# ProPrj_Flipper_-_TweenWave_2025-09-02.net
KiCad netlist of a schematic drawn in EasyEDA Pro
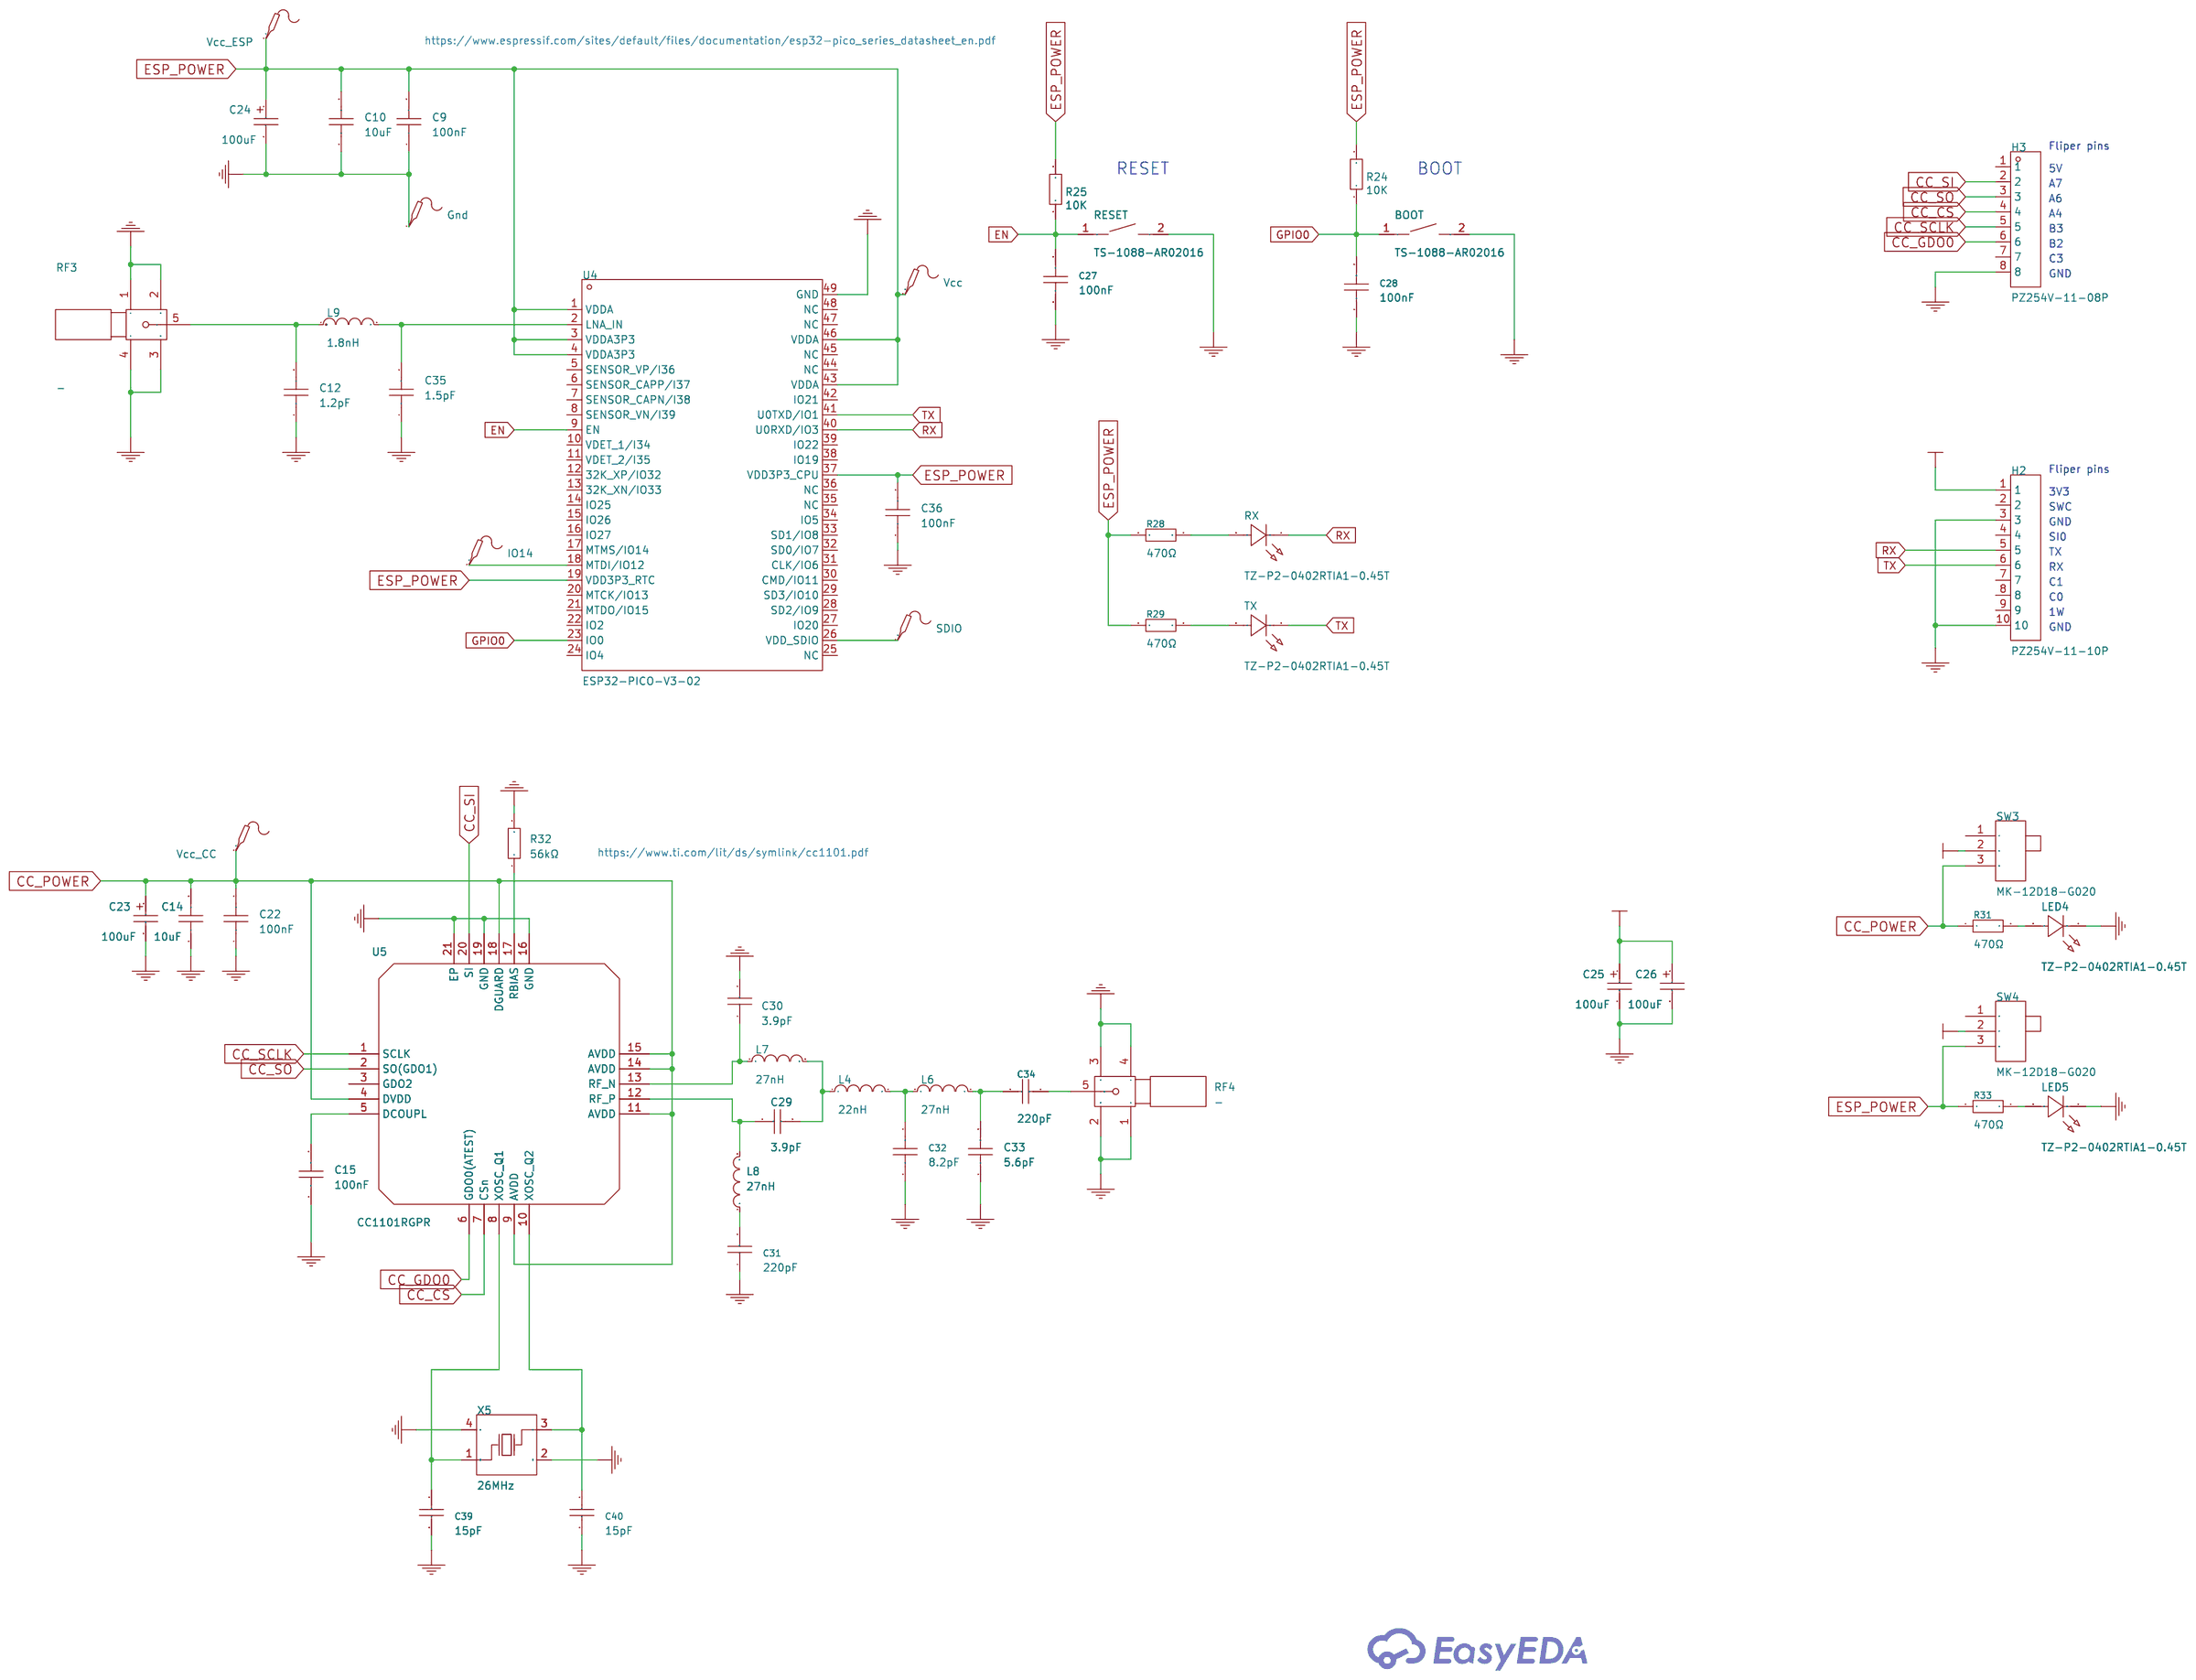
[diagram p0: schematic sheet]

(export (version "E")
  (design (tool "Eeschema 10.0.6"))
  (components
    (comp (ref "BOOT")
      (value "TS-1088-AR02016")
      (footprint "easyedapro:SW-SMD_L3.9-W3.0-P4.45")
      (fields (field (name "Manufacturer") "XUNPU(讯普)"))
      (libsource (lib "easyedapro") (part "TS-1088-AR02016"))
    )
    (comp (ref "C9")
      (value "100nF")
      (footprint "easyedapro:C0603")
      (description "Capacitance:100nF Tolerance:±10% Tolerance:±10% Voltage Rating:50V Temperature Coefficient:X7R")
      (fields
        (field (name "Manufacturer Part") "CC0603KRX7R9BB104")
        (field (name "Manufacturer") "YAGEO(国巨)")
      )
      (libsource (lib "easyedapro") (part "CC0603KRX7R9BB104"))
    )
    (comp (ref "C10")
      (value "10uF")
      (footprint "easyedapro:C0603")
      (fields
        (field (name "Manufacturer Part") "CL10A106MP8NNNC")
        (field (name "Manufacturer") "SAMSUNG(三星)")
      )
      (libsource (lib "easyedapro") (part "CL10A106MP8NNNC"))
    )
    (comp (ref "C12")
      (value "1.2pF")
      (footprint "easyedapro:C0201")
      (fields
        (field (name "Manufacturer Part") "GRM0335C1H1R2BA01D")
        (field (name "Manufacturer") "muRata(村田)")
      )
      (libsource (lib "easyedapro") (part "GRM0335C1H1R2BA01D"))
    )
    (comp (ref "C14")
      (value "10uF")
      (footprint "easyedapro:C0603")
      (fields
        (field (name "Manufacturer Part") "CL10A106MP8NNNC")
        (field (name "Manufacturer") "SAMSUNG(三星)")
      )
      (libsource (lib "easyedapro") (part "CL10A106MP8NNNC"))
    )
    (comp (ref "C15")
      (value "100nF")
      (footprint "easyedapro:C0603")
      (description "Capacitance:100nF Tolerance:±10% Tolerance:±10% Voltage Rating:50V Temperature Coefficient:X7R")
      (fields
        (field (name "Manufacturer Part") "CC0603KRX7R9BB104")
        (field (name "Manufacturer") "YAGEO(国巨)")
      )
      (libsource (lib "easyedapro") (part "CC0603KRX7R9BB104"))
    )
    (comp (ref "C22")
      (value "100nF")
      (footprint "easyedapro:C0603")
      (description "Capacitance:100nF Tolerance:±10% Tolerance:±10% Voltage Rating:50V Temperature Coefficient:X7R")
      (fields
        (field (name "Manufacturer Part") "CC0603KRX7R9BB104")
        (field (name "Manufacturer") "YAGEO(国巨)")
      )
      (libsource (lib "easyedapro") (part "CC0603KRX7R9BB104"))
    )
    (comp (ref "C23")
      (value "100uF")
      (footprint "easyedapro:CASE-B_3528")
      (fields (field (name "Manufacturer Part") "TAJB107K006RNJ") (field (name "Manufacturer") "Kyocera AVX"))
      (libsource (lib "easyedapro") (part "TAJB107K006RNJ"))
    )
    (comp (ref "C24")
      (value "100uF")
      (footprint "easyedapro:CASE-B_3528")
      (fields (field (name "Manufacturer Part") "TAJB107K006RNJ") (field (name "Manufacturer") "Kyocera AVX"))
      (libsource (lib "easyedapro") (part "TAJB107K006RNJ"))
    )
    (comp (ref "C25")
      (value "100uF")
      (footprint "easyedapro:CASE-B_3528")
      (fields (field (name "Manufacturer Part") "TAJB107K006RNJ") (field (name "Manufacturer") "Kyocera AVX"))
      (libsource (lib "easyedapro") (part "TAJB107K006RNJ"))
    )
    (comp (ref "C26")
      (value "100uF")
      (footprint "easyedapro:CASE-B_3528")
      (fields (field (name "Manufacturer Part") "TAJB107K006RNJ") (field (name "Manufacturer") "Kyocera AVX"))
      (libsource (lib "easyedapro") (part "TAJB107K006RNJ"))
    )
    (comp (ref "C27")
      (value "100nF")
      (footprint "easyedapro:C0402")
      (fields
        (field (name "Manufacturer Part") "CC0402KRX7R7BB104")
        (field (name "Manufacturer") "YAGEO(国巨)")
      )
      (libsource (lib "easyedapro") (part "CC0402KRX7R7BB104"))
    )
    (comp (ref "C28")
      (value "100nF")
      (footprint "easyedapro:C0402")
      (fields
        (field (name "Manufacturer Part") "CC0402KRX7R7BB104")
        (field (name "Manufacturer") "YAGEO(国巨)")
      )
      (libsource (lib "easyedapro") (part "CC0402KRX7R7BB104"))
    )
    (comp (ref "C29")
      (value "3.9pF")
      (footprint "easyedapro:C0402")
      (fields (field (name "Manufacturer Part") "0402CG3R9C500NT") (field (name "Manufacturer") "FH(风华)"))
      (libsource (lib "easyedapro") (part "0402CG3R9C500NT"))
    )
    (comp (ref "C30")
      (value "3.9pF")
      (footprint "easyedapro:C0402")
      (fields (field (name "Manufacturer Part") "0402CG3R9C500NT") (field (name "Manufacturer") "FH(风华)"))
      (libsource (lib "easyedapro") (part "0402CG3R9C500NT"))
    )
    (comp (ref "C31")
      (value "220pF")
      (footprint "easyedapro:C0402")
      (description "Capacitance:220pF Tolerance:±5% Tolerance:±5% Voltage Rating:50V Temperature Coefficient:NP0")
      (fields
        (field (name "Manufacturer Part") "CC0402JRNPO9BN221")
        (field (name "Manufacturer") "YAGEO(国巨)")
      )
      (libsource (lib "easyedapro") (part "CC0402JRNPO9BN221"))
    )
    (comp (ref "C32")
      (value "8.2pF")
      (footprint "easyedapro:C0402")
      (fields
        (field (name "Manufacturer Part") "CC0402BRNPO9BN8R2")
        (field (name "Manufacturer") "YAGEO(国巨)")
      )
      (libsource (lib "easyedapro") (part "CC0402BRNPO9BN8R2"))
    )
    (comp (ref "C33")
      (value "5.6pF")
      (footprint "easyedapro:C0402")
      (fields
        (field (name "Manufacturer Part") "CC0402BRNPO9BN5R6")
        (field (name "Manufacturer") "YAGEO(国巨)")
      )
      (libsource (lib "easyedapro") (part "CC0402BRNPO9BN5R6"))
    )
    (comp (ref "C34")
      (value "220pF")
      (footprint "easyedapro:C0402")
      (description "Capacitance:220pF Tolerance:±5% Tolerance:±5% Voltage Rating:50V Temperature Coefficient:NP0")
      (fields
        (field (name "Manufacturer Part") "CC0402JRNPO9BN221")
        (field (name "Manufacturer") "YAGEO(国巨)")
      )
      (libsource (lib "easyedapro") (part "CC0402JRNPO9BN221"))
    )
    (comp (ref "C35")
      (value "1.5pF")
      (footprint "easyedapro:C0201")
      (fields
        (field (name "Manufacturer Part") "GRM0335C1H1R5BA01D")
        (field (name "Manufacturer") "muRata(村田)")
      )
      (libsource (lib "easyedapro") (part "GRM0335C1H1R5BA01D"))
    )
    (comp (ref "C36")
      (value "100nF")
      (footprint "easyedapro:C0603")
      (description "Capacitance:100nF Tolerance:±10% Tolerance:±10% Voltage Rating:50V Temperature Coefficient:X7R")
      (fields
        (field (name "Manufacturer Part") "CC0603KRX7R9BB104")
        (field (name "Manufacturer") "YAGEO(国巨)")
      )
      (libsource (lib "easyedapro") (part "CC0603KRX7R9BB104"))
    )
    (comp (ref "C39")
      (value "15pF")
      (footprint "easyedapro:C0402")
      (fields
        (field (name "Manufacturer Part") "CC0402JRNPO9BN150")
        (field (name "Manufacturer") "YAGEO(国巨)")
      )
      (libsource (lib "easyedapro") (part "CC0402JRNPO9BN150"))
    )
    (comp (ref "C40")
      (value "15pF")
      (footprint "easyedapro:C0402")
      (fields
        (field (name "Manufacturer Part") "CC0402JRNPO9BN150")
        (field (name "Manufacturer") "YAGEO(国巨)")
      )
      (libsource (lib "easyedapro") (part "CC0402JRNPO9BN150"))
    )
    (comp (ref "Gnd")
      (value "~")
      (footprint "easyedapro:Test-Point-0.5mm")
      (description "Test Point 测试点")
      (libsource (lib "easyedapro") (part "Test-Point"))
    )
    (comp (ref "H2")
      (value "PZ254V-11-10P")
      (footprint "easyedapro:HDR-TH_10P-P2.54-V-M")
      (fields (field (name "Manufacturer") "XFCN(兴飞)"))
      (libsource (lib "easyedapro") (part "PZ254V-11-10P"))
    )
    (comp (ref "H3")
      (value "PZ254V-11-08P")
      (footprint "easyedapro:HDR-TH_8P-P2.54-V-M")
      (fields (field (name "Manufacturer") "XFCN(兴飞)"))
      (libsource (lib "easyedapro") (part "PZ254V-11-08P"))
    )
    (comp (ref "IO14")
      (value "~")
      (footprint "easyedapro:Test-Point-0.5mm")
      (description "Test Point 测试点")
      (libsource (lib "easyedapro") (part "Test-Point"))
    )
    (comp (ref "L4")
      (value "22nH")
      (footprint "easyedapro:L0402")
      (fields (field (name "Manufacturer Part") "LQG15HS22NJ02D") (field (name "Manufacturer") "muRata(村田)"))
      (libsource (lib "easyedapro") (part "LQG15HS22NJ02D"))
    )
    (comp (ref "L6")
      (value "27nH")
      (footprint "easyedapro:L0402-RD")
      (fields (field (name "Manufacturer Part") "LQG15HS27NJ02D") (field (name "Manufacturer") "muRata(村田)"))
      (libsource (lib "easyedapro") (part "LQG15HS27NJ02D"))
    )
    (comp (ref "L7")
      (value "27nH")
      (footprint "easyedapro:L0402-RD")
      (fields (field (name "Manufacturer Part") "LQG15HS27NJ02D") (field (name "Manufacturer") "muRata(村田)"))
      (libsource (lib "easyedapro") (part "LQG15HS27NJ02D"))
    )
    (comp (ref "L8")
      (value "27nH")
      (footprint "easyedapro:L0402-RD")
      (fields (field (name "Manufacturer Part") "LQG15HS27NJ02D") (field (name "Manufacturer") "muRata(村田)"))
      (libsource (lib "easyedapro") (part "LQG15HS27NJ02D"))
    )
    (comp (ref "L9")
      (value "1.8nH")
      (footprint "easyedapro:L0201-RD")
      (fields (field (name "Manufacturer Part") "LQP03TN1N8B02D") (field (name "Manufacturer") "muRata(村田)"))
      (libsource (lib "easyedapro") (part "LQP03TN1N8B02D"))
    )
    (comp (ref "LED4")
      (value "TZ-P2-0402RTIA1-0.45T")
      (footprint "easyedapro:LED0402-RD_RED")
      (fields (field (name "Manufacturer") "TUOZHAN(拓展光电)"))
      (libsource (lib "easyedapro") (part "TZ-P2-0402RTIA1-0.45T"))
    )
    (comp (ref "LED5")
      (value "TZ-P2-0402RTIA1-0.45T")
      (footprint "easyedapro:LED0402-RD_RED")
      (fields (field (name "Manufacturer") "TUOZHAN(拓展光电)"))
      (libsource (lib "easyedapro") (part "TZ-P2-0402RTIA1-0.45T"))
    )
    (comp (ref "R24")
      (value "10K")
      (footprint "easyedapro:R0603")
      (fields (field (name "Manufacturer Part") "RC0603DR-0710KL") (field (name "Manufacturer") "YAGEO(国巨)"))
      (libsource (lib "easyedapro") (part "10K"))
    )
    (comp (ref "R25")
      (value "10K")
      (footprint "easyedapro:R0603")
      (fields (field (name "Manufacturer Part") "RC0603DR-0710KL") (field (name "Manufacturer") "YAGEO(国巨)"))
      (libsource (lib "easyedapro") (part "10K"))
    )
    (comp (ref "R28")
      (value "470Ω")
      (footprint "easyedapro:R0402")
      (fields
        (field (name "Manufacturer Part") "0402WGF4700TCE")
        (field (name "Manufacturer") "UNI-ROYAL(厚声)")
      )
      (libsource (lib "easyedapro") (part "0402WGF4700TCE"))
    )
    (comp (ref "R29")
      (value "470Ω")
      (footprint "easyedapro:R0402")
      (fields
        (field (name "Manufacturer Part") "0402WGF4700TCE")
        (field (name "Manufacturer") "UNI-ROYAL(厚声)")
      )
      (libsource (lib "easyedapro") (part "0402WGF4700TCE"))
    )
    (comp (ref "R31")
      (value "470Ω")
      (footprint "easyedapro:R0402")
      (fields
        (field (name "Manufacturer Part") "0402WGF4700TCE")
        (field (name "Manufacturer") "UNI-ROYAL(厚声)")
      )
      (libsource (lib "easyedapro") (part "0402WGF4700TCE"))
    )
    (comp (ref "R32")
      (value "56kΩ")
      (footprint "easyedapro:R0402")
      (fields
        (field (name "Manufacturer Part") "0402WGF5602TCE")
        (field (name "Manufacturer") "UNI-ROYAL(厚声)")
      )
      (libsource (lib "easyedapro") (part "0402WGF5602TCE"))
    )
    (comp (ref "R33")
      (value "470Ω")
      (footprint "easyedapro:R0402")
      (fields
        (field (name "Manufacturer Part") "0402WGF4700TCE")
        (field (name "Manufacturer") "UNI-ROYAL(厚声)")
      )
      (libsource (lib "easyedapro") (part "0402WGF4700TCE"))
    )
    (comp (ref "RESET")
      (value "TS-1088-AR02016")
      (footprint "easyedapro:SW-SMD_L3.9-W3.0-P4.45")
      (fields (field (name "Manufacturer") "XUNPU(讯普)"))
      (libsource (lib "easyedapro") (part "TS-1088-AR02016"))
    )
    (comp (ref "RF3")
      (value "-")
      (footprint "easyedapro:SMA-SMD_BWSMA-KE-P001")
      (fields
        (field (name "Manufacturer Part") "BWSMA-KE-P001")
        (field (name "Manufacturer") "BAT WIRELESS(蝙蝠无线)")
      )
      (libsource (lib "easyedapro") (part "BWSMA-KE-P001"))
    )
    (comp (ref "RF4")
      (value "-")
      (footprint "easyedapro:SMA-SMD_BWSMA-KE-P001")
      (fields
        (field (name "Manufacturer Part") "BWSMA-KE-P001")
        (field (name "Manufacturer") "BAT WIRELESS(蝙蝠无线)")
      )
      (libsource (lib "easyedapro") (part "BWSMA-KE-P001"))
    )
    (comp (ref "RX")
      (value "TZ-P2-0402RTIA1-0.45T")
      (footprint "easyedapro:LED0402-RD_RED")
      (fields (field (name "Manufacturer") "TUOZHAN(拓展光电)"))
      (libsource (lib "easyedapro") (part "TZ-P2-0402RTIA1-0.45T"))
    )
    (comp (ref "SDIO")
      (value "~")
      (footprint "easyedapro:Test-Point-0.5mm")
      (description "Test Point 测试点")
      (libsource (lib "easyedapro") (part "Test-Point"))
    )
    (comp (ref "SW3")
      (value "MK-12D18-G020")
      (footprint "easyedapro:SW-TH_MK-12D18-G040")
      (fields (field (name "Manufacturer") "G-Switch(品赞)"))
      (libsource (lib "easyedapro") (part "MK-12D18-G020"))
    )
    (comp (ref "SW4")
      (value "MK-12D18-G020")
      (footprint "easyedapro:SW-TH_MK-12D18-G040")
      (fields (field (name "Manufacturer") "G-Switch(品赞)"))
      (libsource (lib "easyedapro") (part "MK-12D18-G020"))
    )
    (comp (ref "TX")
      (value "TZ-P2-0402RTIA1-0.45T")
      (footprint "easyedapro:LED0402-RD_RED")
      (fields (field (name "Manufacturer") "TUOZHAN(拓展光电)"))
      (libsource (lib "easyedapro") (part "TZ-P2-0402RTIA1-0.45T"))
    )
    (comp (ref "U4")
      (value "ESP32-PICO-V3-02")
      (footprint "easyedapro:QFN-48_L7.0-W7.0-P0.50-BL-EP5.1")
      (fields (field (name "Manufacturer") "ESPRESSIF(乐鑫)"))
      (libsource (lib "easyedapro") (part "ESP32-PICO-V3-02"))
    )
    (comp (ref "U5")
      (value "CC1101RGPR")
      (footprint "easyedapro:QFN-20_L4.0-W4.0-P0.5-TL-EP")
      (fields (field (name "Manufacturer") "TI(德州仪器)"))
      (libsource (lib "easyedapro") (part "CC1101RGPR"))
    )
    (comp (ref "Vcc")
      (value "~")
      (footprint "easyedapro:Test-Point-0.5mm")
      (description "Test Point 测试点")
      (libsource (lib "easyedapro") (part "Test-Point"))
    )
    (comp (ref "Vcc_CC")
      (value "~")
      (footprint "easyedapro:Test-Point-0.5mm")
      (description "Test Point 测试点")
      (libsource (lib "easyedapro") (part "Test-Point"))
    )
    (comp (ref "Vcc_ESP")
      (value "~")
      (footprint "easyedapro:Test-Point-0.5mm")
      (description "Test Point 测试点")
      (libsource (lib "easyedapro") (part "Test-Point"))
    )
    (comp (ref "X5")
      (value "26MHz")
      (footprint "easyedapro:CRYSTAL-SMD_4P-L3.2-W2.5-BL")
      (fields (field (name "Manufacturer Part") "X322526MMB4SI") (field (name "Manufacturer") "YXC(扬兴晶振)"))
      (libsource (lib "easyedapro") (part "X322526MMB4SI"))
    )
  )
  (nets
    (net (code "1") (name "3V3") (class "Default")
      (node (ref "C25") (pin "1") (pinfunction "1_1") (pintype "input"))
      (node (ref "C26") (pin "1") (pinfunction "1_1") (pintype "input"))
      (node (ref "H2") (pin "1") (pinfunction "1_1") (pintype "unspecified"))
      (node (ref "SW3") (pin "2") (pinfunction "2_2") (pintype "unspecified"))
      (node (ref "SW4") (pin "2") (pinfunction "2_2") (pintype "unspecified"))
    )
    (net (code "2") (name "CC_CS") (class "Default")
      (node (ref "H3") (pin "4") (pinfunction "4_4") (pintype "unspecified"))
      (node (ref "U5") (pin "7") (pinfunction "CSn_7") (pintype "unspecified"))
    )
    (net (code "3") (name "CC_GDO0") (class "Default")
      (node (ref "H3") (pin "6") (pinfunction "6_6") (pintype "unspecified"))
      (node (ref "U5") (pin "6") (pinfunction "GDO0(ATEST)_6") (pintype "unspecified"))
    )
    (net (code "4") (name "CC_POWER") (class "Default")
      (node (ref "C14") (pin "2") (pinfunction "2_2") (pintype "unspecified"))
      (node (ref "C22") (pin "2") (pinfunction "2_2") (pintype "unspecified"))
      (node (ref "C23") (pin "1") (pinfunction "1_1") (pintype "input"))
      (node (ref "R31") (pin "1") (pinfunction "1_1") (pintype "input"))
      (node (ref "SW3") (pin "3") (pinfunction "3_3") (pintype "unspecified"))
      (node (ref "U5") (pin "11") (pinfunction "AVDD_11") (pintype "unspecified"))
      (node (ref "U5") (pin "14") (pinfunction "AVDD_14") (pintype "unspecified"))
      (node (ref "U5") (pin "15") (pinfunction "AVDD_15") (pintype "unspecified"))
      (node (ref "U5") (pin "18") (pinfunction "DGUARD_18") (pintype "unspecified"))
      (node (ref "U5") (pin "4") (pinfunction "DVDD_4") (pintype "unspecified"))
      (node (ref "U5") (pin "9") (pinfunction "AVDD_9") (pintype "unspecified"))
      (node (ref "Vcc_CC") (pin "1") (pinfunction "1_1") (pintype "unspecified"))
    )
    (net (code "5") (name "CC_SCLK") (class "Default")
      (node (ref "H3") (pin "5") (pinfunction "5_5") (pintype "unspecified"))
      (node (ref "U5") (pin "1") (pinfunction "SCLK_1") (pintype "unspecified"))
    )
    (net (code "6") (name "CC_SI") (class "Default")
      (node (ref "H3") (pin "2") (pinfunction "2_2") (pintype "unspecified"))
      (node (ref "U5") (pin "20") (pinfunction "SI_20") (pintype "unspecified"))
    )
    (net (code "7") (name "CC_SO") (class "Default")
      (node (ref "H3") (pin "3") (pinfunction "3_3") (pintype "unspecified"))
      (node (ref "U5") (pin "2") (pinfunction "SO(GDO1)_2") (pintype "unspecified"))
    )
    (net (code "8") (name "EN") (class "Default")
      (node (ref "C27") (pin "2") (pinfunction "2_2") (pintype "input"))
      (node (ref "R25") (pin "1") (pinfunction "1_1") (pintype "input"))
      (node (ref "RESET") (pin "1") (pinfunction "1_1") (pintype "unspecified"))
      (node (ref "U4") (pin "9") (pinfunction "EN_9") (pintype "unspecified"))
    )
    (net (code "9") (name "ESP_POWER") (class "Default")
      (node (ref "C10") (pin "2") (pinfunction "2_2") (pintype "unspecified"))
      (node (ref "C24") (pin "1") (pinfunction "1_1") (pintype "input"))
      (node (ref "C36") (pin "2") (pinfunction "2_2") (pintype "unspecified"))
      (node (ref "C9") (pin "2") (pinfunction "2_2") (pintype "unspecified"))
      (node (ref "R24") (pin "2") (pinfunction "2_2") (pintype "input"))
      (node (ref "R25") (pin "2") (pinfunction "2_2") (pintype "input"))
      (node (ref "R28") (pin "1") (pinfunction "1_1") (pintype "input"))
      (node (ref "R29") (pin "1") (pinfunction "1_1") (pintype "input"))
      (node (ref "R33") (pin "1") (pinfunction "1_1") (pintype "input"))
      (node (ref "SW4") (pin "3") (pinfunction "3_3") (pintype "unspecified"))
      (node (ref "U4") (pin "1") (pinfunction "VDDA_1") (pintype "unspecified"))
      (node (ref "U4") (pin "19") (pinfunction "VDD3P3_RTC_19") (pintype "unspecified"))
      (node (ref "U4") (pin "3") (pinfunction "VDDA3P3_3") (pintype "unspecified"))
      (node (ref "U4") (pin "37") (pinfunction "VDD3P3_CPU_37") (pintype "unspecified"))
      (node (ref "U4") (pin "4") (pinfunction "VDDA3P3_4") (pintype "unspecified"))
      (node (ref "U4") (pin "43") (pinfunction "VDDA_43") (pintype "unspecified"))
      (node (ref "U4") (pin "46") (pinfunction "VDDA_46") (pintype "unspecified"))
      (node (ref "Vcc") (pin "1") (pinfunction "1_1") (pintype "unspecified"))
      (node (ref "Vcc_ESP") (pin "1") (pinfunction "1_1") (pintype "unspecified"))
    )
    (net (code "10") (name "GND") (class "Default")
      (node (ref "BOOT") (pin "2") (pinfunction "2_2") (pintype "unspecified"))
      (node (ref "C10") (pin "1") (pinfunction "1_1") (pintype "unspecified"))
      (node (ref "C12") (pin "1") (pinfunction "1_1") (pintype "unspecified"))
      (node (ref "C14") (pin "1") (pinfunction "1_1") (pintype "unspecified"))
      (node (ref "C15") (pin "1") (pinfunction "1_1") (pintype "unspecified"))
      (node (ref "C22") (pin "1") (pinfunction "1_1") (pintype "unspecified"))
      (node (ref "C23") (pin "2") (pinfunction "2_2") (pintype "input"))
      (node (ref "C24") (pin "2") (pinfunction "2_2") (pintype "input"))
      (node (ref "C25") (pin "2") (pinfunction "2_2") (pintype "input"))
      (node (ref "C26") (pin "2") (pinfunction "2_2") (pintype "input"))
      (node (ref "C27") (pin "1") (pinfunction "1_1") (pintype "input"))
      (node (ref "C28") (pin "1") (pinfunction "1_1") (pintype "input"))
      (node (ref "C30") (pin "2") (pinfunction "2_2") (pintype "input"))
      (node (ref "C31") (pin "1") (pinfunction "1_1") (pintype "input"))
      (node (ref "C32") (pin "2") (pinfunction "2_2") (pintype "input"))
      (node (ref "C33") (pin "1") (pinfunction "1_1") (pintype "unspecified"))
      (node (ref "C35") (pin "1") (pinfunction "1_1") (pintype "unspecified"))
      (node (ref "C36") (pin "1") (pinfunction "1_1") (pintype "unspecified"))
      (node (ref "C39") (pin "1") (pinfunction "1_1") (pintype "input"))
      (node (ref "C40") (pin "1") (pinfunction "1_1") (pintype "input"))
      (node (ref "C9") (pin "1") (pinfunction "1_1") (pintype "unspecified"))
      (node (ref "Gnd") (pin "1") (pinfunction "1_1") (pintype "unspecified"))
      (node (ref "H2") (pin "10") (pinfunction "10_10") (pintype "unspecified"))
      (node (ref "H2") (pin "3") (pinfunction "3_3") (pintype "unspecified"))
      (node (ref "H3") (pin "8") (pinfunction "8_8") (pintype "unspecified"))
      (node (ref "LED4") (pin "1") (pinfunction "K_1") (pintype "unspecified"))
      (node (ref "LED5") (pin "1") (pinfunction "K_1") (pintype "unspecified"))
      (node (ref "R32") (pin "2") (pinfunction "2_2") (pintype "input"))
      (node (ref "RESET") (pin "2") (pinfunction "2_2") (pintype "unspecified"))
      (node (ref "RF3") (pin "1") (pinfunction "1_1") (pintype "unspecified"))
      (node (ref "RF3") (pin "2") (pinfunction "2_2") (pintype "unspecified"))
      (node (ref "RF3") (pin "3") (pinfunction "3_3") (pintype "unspecified"))
      (node (ref "RF3") (pin "4") (pinfunction "4_4") (pintype "unspecified"))
      (node (ref "RF4") (pin "1") (pinfunction "1_1") (pintype "unspecified"))
      (node (ref "RF4") (pin "2") (pinfunction "2_2") (pintype "unspecified"))
      (node (ref "RF4") (pin "3") (pinfunction "3_3") (pintype "unspecified"))
      (node (ref "RF4") (pin "4") (pinfunction "4_4") (pintype "unspecified"))
      (node (ref "U4") (pin "49") (pinfunction "GND_49") (pintype "unspecified"))
      (node (ref "U5") (pin "16") (pinfunction "GND_16") (pintype "unspecified"))
      (node (ref "U5") (pin "19") (pinfunction "GND_19") (pintype "unspecified"))
      (node (ref "U5") (pin "21") (pinfunction "EP_21") (pintype "unspecified"))
      (node (ref "X5") (pin "2") (pinfunction "GND_2") (pintype "unspecified"))
      (node (ref "X5") (pin "4") (pinfunction "GND_4") (pintype "unspecified"))
    )
    (net (code "11") (name "GPIO0") (class "Default")
      (node (ref "BOOT") (pin "1") (pinfunction "1_1") (pintype "unspecified"))
      (node (ref "C28") (pin "2") (pinfunction "2_2") (pintype "input"))
      (node (ref "R24") (pin "1") (pinfunction "1_1") (pintype "input"))
      (node (ref "U4") (pin "23") (pinfunction "IO0_23") (pintype "unspecified"))
    )
    (net (code "12") (name "Net-(C12-Pad2)") (class "Default")
      (node (ref "C12") (pin "2") (pinfunction "2_2") (pintype "unspecified"))
      (node (ref "L9") (pin "1") (pinfunction "1_1") (pintype "input"))
      (node (ref "RF3") (pin "5") (pinfunction "5_5") (pintype "unspecified"))
    )
    (net (code "13") (name "Net-(C29-Pad2)") (class "Default")
      (node (ref "C29") (pin "2") (pinfunction "2_2") (pintype "input"))
      (node (ref "L4") (pin "1") (pinfunction "1_1") (pintype "unspecified"))
      (node (ref "L7") (pin "2") (pinfunction "2_2") (pintype "unspecified"))
    )
    (net (code "14") (name "Net-(C31-Pad2)") (class "Default")
      (node (ref "C31") (pin "2") (pinfunction "2_2") (pintype "input"))
      (node (ref "L8") (pin "1") (pinfunction "1_1") (pintype "unspecified"))
    )
    (net (code "15") (name "Net-(C32-Pad1)") (class "Default")
      (node (ref "C32") (pin "1") (pinfunction "1_1") (pintype "input"))
      (node (ref "L4") (pin "2") (pinfunction "2_2") (pintype "unspecified"))
      (node (ref "L6") (pin "1") (pinfunction "1_1") (pintype "unspecified"))
    )
    (net (code "16") (name "Net-(C33-Pad2)") (class "Default")
      (node (ref "C33") (pin "2") (pinfunction "2_2") (pintype "unspecified"))
      (node (ref "C34") (pin "2") (pinfunction "2_2") (pintype "input"))
      (node (ref "L6") (pin "2") (pinfunction "2_2") (pintype "unspecified"))
    )
    (net (code "17") (name "Net-(C34-Pad1)") (class "Default")
      (node (ref "C34") (pin "1") (pinfunction "1_1") (pintype "input"))
      (node (ref "RF4") (pin "5") (pinfunction "5_5") (pintype "unspecified"))
    )
    (net (code "18") (name "Net-(LED4-A)") (class "Default")
      (node (ref "LED4") (pin "2") (pinfunction "A_2") (pintype "unspecified"))
      (node (ref "R31") (pin "2") (pinfunction "2_2") (pintype "input"))
    )
    (net (code "19") (name "Net-(LED5-A)") (class "Default")
      (node (ref "LED5") (pin "2") (pinfunction "A_2") (pintype "unspecified"))
      (node (ref "R33") (pin "2") (pinfunction "2_2") (pintype "input"))
    )
    (net (code "20") (name "Net-(RX-A)") (class "Default")
      (node (ref "R28") (pin "2") (pinfunction "2_2") (pintype "input"))
      (node (ref "RX") (pin "2") (pinfunction "A_2") (pintype "unspecified"))
    )
    (net (code "21") (name "Net-(TX-A)") (class "Default")
      (node (ref "R29") (pin "2") (pinfunction "2_2") (pintype "input"))
      (node (ref "TX") (pin "2") (pinfunction "A_2") (pintype "unspecified"))
    )
    (net (code "22") (name "Net-(U4-LNA_IN)") (class "Default")
      (node (ref "C35") (pin "2") (pinfunction "2_2") (pintype "unspecified"))
      (node (ref "L9") (pin "2") (pinfunction "2_2") (pintype "input"))
      (node (ref "U4") (pin "2") (pinfunction "LNA_IN_2") (pintype "unspecified"))
    )
    (net (code "23") (name "Net-(U4-MTDI{slash}IO12)") (class "Default")
      (node (ref "IO14") (pin "1") (pinfunction "1_1") (pintype "unspecified"))
      (node (ref "U4") (pin "18") (pinfunction "MTDI/IO12_18") (pintype "unspecified"))
    )
    (net (code "24") (name "Net-(U4-VDD_SDIO)") (class "Default")
      (node (ref "SDIO") (pin "1") (pinfunction "1_1") (pintype "unspecified"))
      (node (ref "U4") (pin "26") (pinfunction "VDD_SDIO_26") (pintype "unspecified"))
    )
    (net (code "25") (name "Net-(U5-DCOUPL)") (class "Default")
      (node (ref "C15") (pin "2") (pinfunction "2_2") (pintype "unspecified"))
      (node (ref "U5") (pin "5") (pinfunction "DCOUPL_5") (pintype "unspecified"))
    )
    (net (code "26") (name "Net-(U5-RBIAS)") (class "Default")
      (node (ref "R32") (pin "1") (pinfunction "1_1") (pintype "input"))
      (node (ref "U5") (pin "17") (pinfunction "RBIAS_17") (pintype "unspecified"))
    )
    (net (code "27") (name "Net-(U5-RF_N)") (class "Default")
      (node (ref "C30") (pin "1") (pinfunction "1_1") (pintype "input"))
      (node (ref "L7") (pin "1") (pinfunction "1_1") (pintype "unspecified"))
      (node (ref "U5") (pin "13") (pinfunction "RF_N_13") (pintype "unspecified"))
    )
    (net (code "28") (name "Net-(U5-RF_P)") (class "Default")
      (node (ref "C29") (pin "1") (pinfunction "1_1") (pintype "input"))
      (node (ref "L8") (pin "2") (pinfunction "2_2") (pintype "unspecified"))
      (node (ref "U5") (pin "12") (pinfunction "RF_P_12") (pintype "unspecified"))
    )
    (net (code "29") (name "Net-(U5-XOSC_Q1)") (class "Default")
      (node (ref "C39") (pin "2") (pinfunction "2_2") (pintype "input"))
      (node (ref "U5") (pin "8") (pinfunction "XOSC_Q1_8") (pintype "unspecified"))
      (node (ref "X5") (pin "1") (pinfunction "OSC1_1") (pintype "unspecified"))
    )
    (net (code "30") (name "Net-(U5-XOSC_Q2)") (class "Default")
      (node (ref "C40") (pin "2") (pinfunction "2_2") (pintype "input"))
      (node (ref "U5") (pin "10") (pinfunction "XOSC_Q2_10") (pintype "unspecified"))
      (node (ref "X5") (pin "3") (pinfunction "OSC2_3") (pintype "unspecified"))
    )
    (net (code "31") (name "RX") (class "Default")
      (node (ref "H2") (pin "5") (pinfunction "5_5") (pintype "unspecified"))
      (node (ref "RX") (pin "1") (pinfunction "K_1") (pintype "unspecified"))
      (node (ref "U4") (pin "40") (pinfunction "U0RXD/IO3_40") (pintype "unspecified"))
    )
    (net (code "32") (name "TX") (class "Default")
      (node (ref "H2") (pin "6") (pinfunction "6_6") (pintype "unspecified"))
      (node (ref "TX") (pin "1") (pinfunction "K_1") (pintype "unspecified"))
      (node (ref "U4") (pin "41") (pinfunction "U0TXD/IO1_41") (pintype "unspecified"))
    )
    (net (code "33") (name "unconnected-(H2-Pad2)") (class "Default")
      (node (ref "H2") (pin "2") (pinfunction "2_2") (pintype "unspecified"))
    )
    (net (code "34") (name "unconnected-(H2-Pad4)") (class "Default")
      (node (ref "H2") (pin "4") (pinfunction "4_4") (pintype "unspecified"))
    )
    (net (code "35") (name "unconnected-(H2-Pad7)") (class "Default")
      (node (ref "H2") (pin "7") (pinfunction "7_7") (pintype "unspecified"))
    )
    (net (code "36") (name "unconnected-(H2-Pad8)") (class "Default")
      (node (ref "H2") (pin "8") (pinfunction "8_8") (pintype "unspecified"))
    )
    (net (code "37") (name "unconnected-(H2-Pad9)") (class "Default")
      (node (ref "H2") (pin "9") (pinfunction "9_9") (pintype "unspecified"))
    )
    (net (code "38") (name "unconnected-(H3-Pad1)") (class "Default")
      (node (ref "H3") (pin "1") (pinfunction "1_1") (pintype "unspecified"))
    )
    (net (code "39") (name "unconnected-(H3-Pad7)") (class "Default")
      (node (ref "H3") (pin "7") (pinfunction "7_7") (pintype "unspecified"))
    )
    (net (code "40") (name "unconnected-(SW3-Pad1)") (class "Default")
      (node (ref "SW3") (pin "1") (pinfunction "1_1") (pintype "unspecified"))
    )
    (net (code "41") (name "unconnected-(SW4-Pad1)") (class "Default")
      (node (ref "SW4") (pin "1") (pinfunction "1_1") (pintype "unspecified"))
    )
    (net (code "42") (name "unconnected-(U4-32K_XN{slash}IO33-Pad13)") (class "Default")
      (node (ref "U4") (pin "13") (pinfunction "32K_XN/IO33_13") (pintype "unspecified"))
    )
    (net (code "43") (name "unconnected-(U4-32K_XP{slash}IO32-Pad12)") (class "Default")
      (node (ref "U4") (pin "12") (pinfunction "32K_XP/IO32_12") (pintype "unspecified"))
    )
    (net (code "44") (name "unconnected-(U4-CLK{slash}IO6-Pad31)") (class "Default")
      (node (ref "U4") (pin "31") (pinfunction "CLK/IO6_31") (pintype "unspecified"))
    )
    (net (code "45") (name "unconnected-(U4-CMD{slash}IO11-Pad30)") (class "Default")
      (node (ref "U4") (pin "30") (pinfunction "CMD/IO11_30") (pintype "unspecified"))
    )
    (net (code "46") (name "unconnected-(U4-IO2-Pad22)") (class "Default")
      (node (ref "U4") (pin "22") (pinfunction "IO2_22") (pintype "unspecified"))
    )
    (net (code "47") (name "unconnected-(U4-IO4-Pad24)") (class "Default")
      (node (ref "U4") (pin "24") (pinfunction "IO4_24") (pintype "unspecified"))
    )
    (net (code "48") (name "unconnected-(U4-IO5-Pad34)") (class "Default")
      (node (ref "U4") (pin "34") (pinfunction "IO5_34") (pintype "unspecified"))
    )
    (net (code "49") (name "unconnected-(U4-IO19-Pad38)") (class "Default")
      (node (ref "U4") (pin "38") (pinfunction "IO19_38") (pintype "unspecified"))
    )
    (net (code "50") (name "unconnected-(U4-IO20-Pad27)") (class "Default")
      (node (ref "U4") (pin "27") (pinfunction "IO20_27") (pintype "unspecified"))
    )
    (net (code "51") (name "unconnected-(U4-IO21-Pad42)") (class "Default")
      (node (ref "U4") (pin "42") (pinfunction "IO21_42") (pintype "unspecified"))
    )
    (net (code "52") (name "unconnected-(U4-IO22-Pad39)") (class "Default")
      (node (ref "U4") (pin "39") (pinfunction "IO22_39") (pintype "unspecified"))
    )
    (net (code "53") (name "unconnected-(U4-IO25-Pad14)") (class "Default")
      (node (ref "U4") (pin "14") (pinfunction "IO25_14") (pintype "unspecified"))
    )
    (net (code "54") (name "unconnected-(U4-IO26-Pad15)") (class "Default")
      (node (ref "U4") (pin "15") (pinfunction "IO26_15") (pintype "unspecified"))
    )
    (net (code "55") (name "unconnected-(U4-IO27-Pad16)") (class "Default")
      (node (ref "U4") (pin "16") (pinfunction "IO27_16") (pintype "unspecified"))
    )
    (net (code "56") (name "unconnected-(U4-MTCK{slash}IO13-Pad20)") (class "Default")
      (node (ref "U4") (pin "20") (pinfunction "MTCK/IO13_20") (pintype "unspecified"))
    )
    (net (code "57") (name "unconnected-(U4-MTDO{slash}IO15-Pad21)") (class "Default")
      (node (ref "U4") (pin "21") (pinfunction "MTDO/IO15_21") (pintype "unspecified"))
    )
    (net (code "58") (name "unconnected-(U4-MTMS{slash}IO14-Pad17)") (class "Default")
      (node (ref "U4") (pin "17") (pinfunction "MTMS/IO14_17") (pintype "unspecified"))
    )
    (net (code "59") (name "unconnected-(U4-NC-Pad25)") (class "Default")
      (node (ref "U4") (pin "25") (pinfunction "NC_25") (pintype "unspecified"))
    )
    (net (code "60") (name "unconnected-(U4-NC-Pad35)") (class "Default")
      (node (ref "U4") (pin "35") (pinfunction "NC_35") (pintype "unspecified"))
    )
    (net (code "61") (name "unconnected-(U4-NC-Pad36)") (class "Default")
      (node (ref "U4") (pin "36") (pinfunction "NC_36") (pintype "unspecified"))
    )
    (net (code "62") (name "unconnected-(U4-NC-Pad44)") (class "Default")
      (node (ref "U4") (pin "44") (pinfunction "NC_44") (pintype "unspecified"))
    )
    (net (code "63") (name "unconnected-(U4-NC-Pad45)") (class "Default")
      (node (ref "U4") (pin "45") (pinfunction "NC_45") (pintype "unspecified"))
    )
    (net (code "64") (name "unconnected-(U4-NC-Pad47)") (class "Default")
      (node (ref "U4") (pin "47") (pinfunction "NC_47") (pintype "unspecified"))
    )
    (net (code "65") (name "unconnected-(U4-NC-Pad48)") (class "Default")
      (node (ref "U4") (pin "48") (pinfunction "NC_48") (pintype "unspecified"))
    )
    (net (code "66") (name "unconnected-(U4-SD0{slash}IO7-Pad32)") (class "Default")
      (node (ref "U4") (pin "32") (pinfunction "SD0/IO7_32") (pintype "unspecified"))
    )
    (net (code "67") (name "unconnected-(U4-SD1{slash}IO8-Pad33)") (class "Default")
      (node (ref "U4") (pin "33") (pinfunction "SD1/IO8_33") (pintype "unspecified"))
    )
    (net (code "68") (name "unconnected-(U4-SD2{slash}IO9-Pad28)") (class "Default")
      (node (ref "U4") (pin "28") (pinfunction "SD2/IO9_28") (pintype "unspecified"))
    )
    (net (code "69") (name "unconnected-(U4-SD3{slash}IO10-Pad29)") (class "Default")
      (node (ref "U4") (pin "29") (pinfunction "SD3/IO10_29") (pintype "unspecified"))
    )
    (net (code "70") (name "unconnected-(U4-SENSOR_CAPN{slash}I38-Pad7)") (class "Default")
      (node (ref "U4") (pin "7") (pinfunction "SENSOR_CAPN/I38_7") (pintype "unspecified"))
    )
    (net (code "71") (name "unconnected-(U4-SENSOR_CAPP{slash}I37-Pad6)") (class "Default")
      (node (ref "U4") (pin "6") (pinfunction "SENSOR_CAPP/I37_6") (pintype "unspecified"))
    )
    (net (code "72") (name "unconnected-(U4-SENSOR_VN{slash}I39-Pad8)") (class "Default")
      (node (ref "U4") (pin "8") (pinfunction "SENSOR_VN/I39_8") (pintype "unspecified"))
    )
    (net (code "73") (name "unconnected-(U4-SENSOR_VP{slash}I36-Pad5)") (class "Default")
      (node (ref "U4") (pin "5") (pinfunction "SENSOR_VP/I36_5") (pintype "unspecified"))
    )
    (net (code "74") (name "unconnected-(U4-VDET_1{slash}I34-Pad10)") (class "Default")
      (node (ref "U4") (pin "10") (pinfunction "VDET_1/I34_10") (pintype "unspecified"))
    )
    (net (code "75") (name "unconnected-(U4-VDET_2{slash}I35-Pad11)") (class "Default")
      (node (ref "U4") (pin "11") (pinfunction "VDET_2/I35_11") (pintype "unspecified"))
    )
    (net (code "76") (name "unconnected-(U5-GDO2-Pad3)") (class "Default")
      (node (ref "U5") (pin "3") (pinfunction "GDO2_3") (pintype "unspecified"))
    )
  )
)
